# Communications.net
KiCad netlist of a schematic drawn in Altium Designer
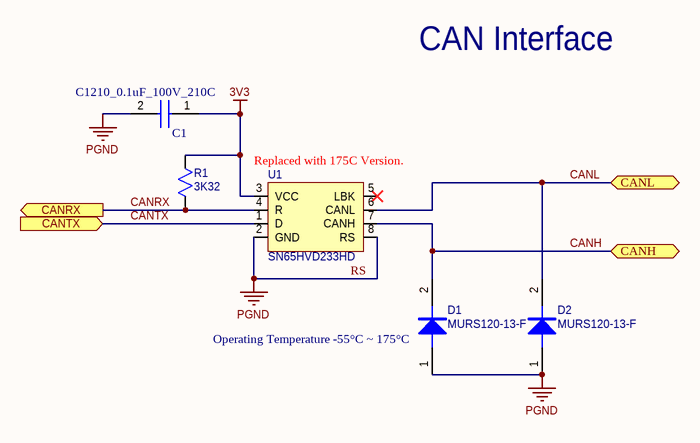
[diagram p0: Communications.SchDoc]

(export (version "E")
  (design (tool "Eeschema 10.0.6"))
  (components
    (comp (ref "C1")
      (value "C1210_0.1uF_100V_210C")
      (footprint "SamacSys:C1210")
      (description "Capacitor")
      (fields
        (field (name "MANUFACTURER_PART_NUMBER") "C1210H104J1GACTU")
        (field (name "MOUSER PART NUMBER") "80-C1210H104J1GACTU")
      )
      (libsource (lib "SamacSys") (part "C1210H104J1GACTU"))
    )
    (comp (ref "D1")
      (value "MURS120-13-F")
      (footprint "SMB-D")
      (description "Diode")
      (fields (field (name "MANUFACTURER") "Diodes Inc."))
      (libsource (lib "Pulser Driver 4,2") (part "DIODE_1"))
    )
    (comp (ref "D2")
      (value "MURS120-13-F")
      (footprint "SMB-D")
      (description "Diode")
      (fields (field (name "MANUFACTURER") "Diodes Inc."))
      (libsource (lib "Pulser Driver 4,2") (part "DIODE_1"))
    )
    (comp (ref "R1")
      (value "3K32")
      (footprint "0603")
      (description "3.32K OHM 1% 1/8W 0603")
      (fields (field (name "MANUFACTURER") "Vishay"))
      (libsource (lib "Resistors") (part "RES_3K32_0603_1%_1/10W"))
    )
    (comp (ref "U1")
      (value "SN65HVD233HD")
      (footprint "D8")
      (description "CAN Transceiver, 3V3")
      (fields (field (name "MANUFACTURER") "TI"))
      (libsource (lib "U-Devices") (part "SN65HVD233HD"))
    )
  )
  (nets
    (net (code "1") (name "/CANH") (class "Default")
      (node (ref "D1") (pin "2") (pinfunction "K_2") (pintype "passive"))
      (node (ref "U1") (pin "7") (pinfunction "CANH_7") (pintype "passive"))
    )
    (net (code "2") (name "/CANL") (class "Default")
      (node (ref "D2") (pin "2") (pinfunction "K_2") (pintype "passive"))
      (node (ref "U1") (pin "6") (pinfunction "CANL_6") (pintype "passive"))
    )
    (net (code "3") (name "/CANRX") (class "Default")
      (node (ref "R1") (pin "1") (pinfunction "1_1") (pintype "passive"))
      (node (ref "U1") (pin "4") (pinfunction "R_4") (pintype "passive"))
    )
    (net (code "4") (name "/CANTX") (class "Default")
      (node (ref "U1") (pin "1") (pinfunction "D_1") (pintype "passive"))
    )
    (net (code "5") (name "3V3") (class "Default")
      (node (ref "C1") (pin "1") (pinfunction "1_1") (pintype "passive"))
      (node (ref "R1") (pin "2") (pinfunction "2_2") (pintype "passive"))
      (node (ref "U1") (pin "3") (pinfunction "VCC_3") (pintype "passive"))
    )
    (net (code "6") (name "PGND") (class "Default")
      (node (ref "C1") (pin "2") (pinfunction "2_2") (pintype "passive"))
      (node (ref "D1") (pin "1") (pinfunction "A_1") (pintype "passive"))
      (node (ref "D2") (pin "1") (pinfunction "A_1") (pintype "passive"))
      (node (ref "U1") (pin "2") (pinfunction "GND_2") (pintype "passive"))
      (node (ref "U1") (pin "8") (pinfunction "RS_8") (pintype "passive"))
    )
    (net (code "7") (name "unconnected-(U1-LBK-Pad5)") (class "Default")
      (node (ref "U1") (pin "5") (pinfunction "LBK_5") (pintype "passive+no_connect"))
    )
  )
)
